# schema_v2_1.net
KiCad netlist of a schematic drawn in EAGLE
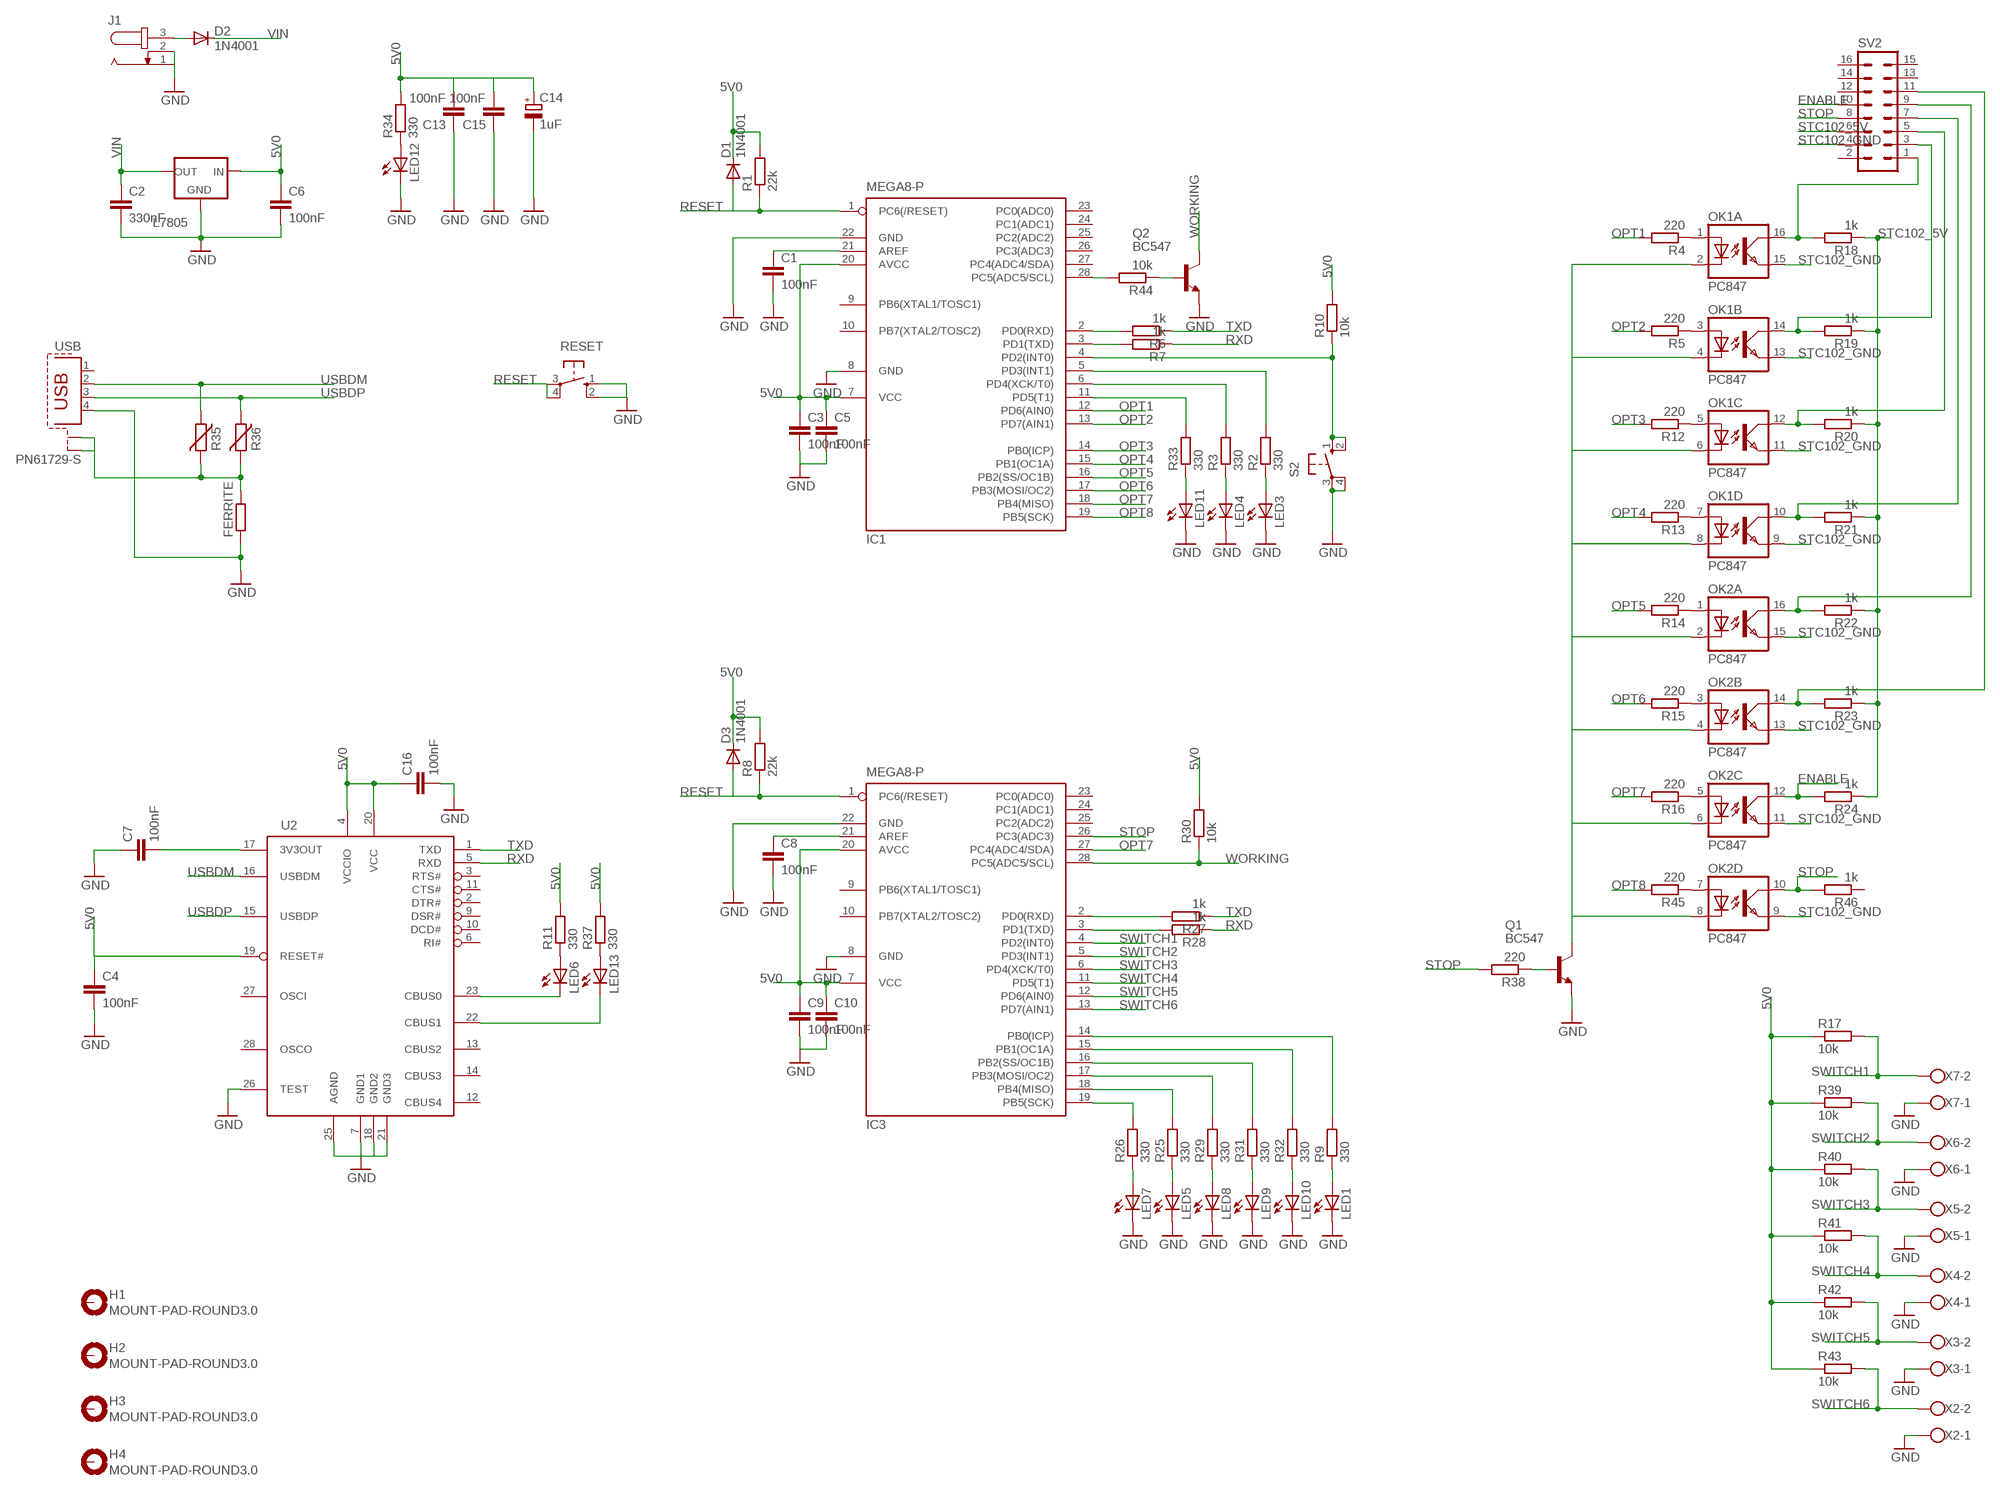
[diagram p0: schematic, sheet 1]

(export (version "E")
  (design (tool "Eeschema 10.0.6"))
  (components
    (comp (ref "C1")
      (value "100nF")
      (footprint "eagle-import:C025-025X050")
      (libsource (lib "eagle-import") (part "C-EU025-025X050"))
    )
    (comp (ref "C2")
      (value "330nF")
      (footprint "eagle-import:C025-025X050")
      (libsource (lib "eagle-import") (part "C-EU025-025X050"))
    )
    (comp (ref "C3")
      (value "100nF")
      (footprint "eagle-import:C025-025X050")
      (libsource (lib "eagle-import") (part "C-EU025-025X050"))
    )
    (comp (ref "C4")
      (value "100nF")
      (footprint "eagle-import:C0603K")
      (libsource (lib "eagle-import") (part "C-EUC0603K"))
    )
    (comp (ref "C5")
      (value "100nF")
      (footprint "eagle-import:C025-025X050")
      (libsource (lib "eagle-import") (part "C-EU025-025X050"))
    )
    (comp (ref "C6")
      (value "100nF")
      (footprint "eagle-import:C025-025X050")
      (libsource (lib "eagle-import") (part "C-EU025-025X050"))
    )
    (comp (ref "C7")
      (value "100nF")
      (footprint "eagle-import:C0603K")
      (libsource (lib "eagle-import") (part "C-EUC0603K"))
    )
    (comp (ref "C8")
      (value "100nF")
      (footprint "eagle-import:C025-025X050")
      (libsource (lib "eagle-import") (part "C-EU025-025X050"))
    )
    (comp (ref "C9")
      (value "100nF")
      (footprint "eagle-import:C025-025X050")
      (libsource (lib "eagle-import") (part "C-EU025-025X050"))
    )
    (comp (ref "C10")
      (value "100nF")
      (footprint "eagle-import:C025-025X050")
      (libsource (lib "eagle-import") (part "C-EU025-025X050"))
    )
    (comp (ref "C13")
      (value "100nF")
      (footprint "eagle-import:C025-025X050")
      (libsource (lib "eagle-import") (part "C-EU025-025X050"))
    )
    (comp (ref "C14")
      (value "1uF")
      (footprint "eagle-import:E2,5-5")
      (libsource (lib "eagle-import") (part "CPOL-EUE2.5-5"))
    )
    (comp (ref "C15")
      (value "100nF")
      (footprint "eagle-import:C025-025X050")
      (libsource (lib "eagle-import") (part "C-EU025-025X050"))
    )
    (comp (ref "C16")
      (value "100nF")
      (footprint "eagle-import:C0603K")
      (libsource (lib "eagle-import") (part "C-EUC0603K"))
    )
    (comp (ref "D1")
      (value "1N4001")
      (footprint "eagle-import:DO41-10")
      (libsource (lib "eagle-import") (part "1N4004"))
    )
    (comp (ref "D2")
      (value "1N4001")
      (footprint "eagle-import:DO41-10")
      (libsource (lib "eagle-import") (part "1N4004"))
    )
    (comp (ref "D3")
      (value "1N4001")
      (footprint "eagle-import:DO41-10")
      (libsource (lib "eagle-import") (part "1N4004"))
    )
    (comp (ref "FERRITE")
      (value "R-EU_M0805")
      (footprint "eagle-import:M0805")
      (libsource (lib "eagle-import") (part "resistor_R-EU_M0805"))
    )
    (comp (ref "H1")
      (value "MOUNT-PAD-ROUND3.0")
      (footprint "eagle-import:3,0-PAD")
      (libsource (lib "eagle-import") (part "MOUNT-PAD-ROUND3.0"))
    )
    (comp (ref "H2")
      (value "MOUNT-PAD-ROUND3.0")
      (footprint "eagle-import:3,0-PAD")
      (libsource (lib "eagle-import") (part "MOUNT-PAD-ROUND3.0"))
    )
    (comp (ref "H3")
      (value "MOUNT-PAD-ROUND3.0")
      (footprint "eagle-import:3,0-PAD")
      (libsource (lib "eagle-import") (part "MOUNT-PAD-ROUND3.0"))
    )
    (comp (ref "H4")
      (value "MOUNT-PAD-ROUND3.0")
      (footprint "eagle-import:3,0-PAD")
      (libsource (lib "eagle-import") (part "MOUNT-PAD-ROUND3.0"))
    )
    (comp (ref "IC1")
      (value "MEGA8-P")
      (footprint "eagle-import:DIL28-3")
      (libsource (lib "eagle-import") (part "MEGA8-P"))
    )
    (comp (ref "IC3")
      (value "MEGA8-P")
      (footprint "eagle-import:DIL28-3")
      (libsource (lib "eagle-import") (part "MEGA8-P"))
    )
    (comp (ref "J1")
      (value "JACK-PLUG0")
      (footprint "eagle-import:SPC4077")
      (libsource (lib "eagle-import") (part "JACK-PLUG0"))
    )
    (comp (ref "L7805")
      (value "79XXS")
      (footprint "eagle-import:79XXS")
      (libsource (lib "eagle-import") (part "79XXS"))
    )
    (comp (ref "LED1")
      (value "LED3MM")
      (footprint "eagle-import:LED3MM")
      (libsource (lib "eagle-import") (part "LED3MM"))
    )
    (comp (ref "LED3")
      (value "LED3MM")
      (footprint "eagle-import:LED3MM")
      (libsource (lib "eagle-import") (part "LED3MM"))
    )
    (comp (ref "LED4")
      (value "LED3MM")
      (footprint "eagle-import:LED3MM")
      (libsource (lib "eagle-import") (part "LED3MM"))
    )
    (comp (ref "LED5")
      (value "LED3MM")
      (footprint "eagle-import:LED3MM")
      (libsource (lib "eagle-import") (part "LED3MM"))
    )
    (comp (ref "LED6")
      (value "LED3MM")
      (footprint "eagle-import:LED3MM")
      (libsource (lib "eagle-import") (part "LED3MM"))
    )
    (comp (ref "LED7")
      (value "LED3MM")
      (footprint "eagle-import:LED3MM")
      (libsource (lib "eagle-import") (part "LED3MM"))
    )
    (comp (ref "LED8")
      (value "LED3MM")
      (footprint "eagle-import:LED3MM")
      (libsource (lib "eagle-import") (part "LED3MM"))
    )
    (comp (ref "LED9")
      (value "LED3MM")
      (footprint "eagle-import:LED3MM")
      (libsource (lib "eagle-import") (part "LED3MM"))
    )
    (comp (ref "LED10")
      (value "LED3MM")
      (footprint "eagle-import:LED3MM")
      (libsource (lib "eagle-import") (part "LED3MM"))
    )
    (comp (ref "LED11")
      (value "LED3MM")
      (footprint "eagle-import:LED3MM")
      (libsource (lib "eagle-import") (part "LED3MM"))
    )
    (comp (ref "LED12")
      (value "LED3MM")
      (footprint "eagle-import:LED3MM")
      (libsource (lib "eagle-import") (part "LED3MM"))
    )
    (comp (ref "LED13")
      (value "LED3MM")
      (footprint "eagle-import:LED3MM")
      (libsource (lib "eagle-import") (part "LED3MM"))
    )
    (comp (ref "OK1")
      (value "PC847")
      (footprint "eagle-import:DIL16")
      (libsource (lib "eagle-import") (part "PC847"))
    )
    (comp (ref "OK2")
      (value "PC847")
      (footprint "eagle-import:DIL16")
      (libsource (lib "eagle-import") (part "PC847"))
    )
    (comp (ref "Q1")
      (value "BC547")
      (footprint "eagle-import:TO92")
      (libsource (lib "eagle-import") (part "BC547"))
    )
    (comp (ref "Q2")
      (value "BC547")
      (footprint "eagle-import:TO92")
      (libsource (lib "eagle-import") (part "BC547"))
    )
    (comp (ref "R1")
      (value "22k")
      (footprint "eagle-import:0207_10")
      (libsource (lib "eagle-import") (part "R-EU_0207/10"))
    )
    (comp (ref "R2")
      (value "330")
      (footprint "eagle-import:0207_10")
      (libsource (lib "eagle-import") (part "R-EU_0207/10"))
    )
    (comp (ref "R3")
      (value "330")
      (footprint "eagle-import:0207_10")
      (libsource (lib "eagle-import") (part "R-EU_0207/10"))
    )
    (comp (ref "R4")
      (value "220")
      (footprint "eagle-import:0207_10")
      (libsource (lib "eagle-import") (part "R-EU_0207/10"))
    )
    (comp (ref "R5")
      (value "220")
      (footprint "eagle-import:0207_10")
      (libsource (lib "eagle-import") (part "R-EU_0207/10"))
    )
    (comp (ref "R6")
      (value "1k")
      (footprint "eagle-import:M1206")
      (libsource (lib "eagle-import") (part "R-EU_M1206"))
    )
    (comp (ref "R7")
      (value "1k")
      (footprint "eagle-import:M1206")
      (libsource (lib "eagle-import") (part "R-EU_M1206"))
    )
    (comp (ref "R8")
      (value "22k")
      (footprint "eagle-import:0207_10")
      (libsource (lib "eagle-import") (part "R-EU_0207/10"))
    )
    (comp (ref "R9")
      (value "330")
      (footprint "eagle-import:0207_10")
      (libsource (lib "eagle-import") (part "R-EU_0207/10"))
    )
    (comp (ref "R10")
      (value "10k")
      (footprint "eagle-import:0207_10")
      (libsource (lib "eagle-import") (part "R-EU_0207/10"))
    )
    (comp (ref "R11")
      (value "330")
      (footprint "eagle-import:0207_10")
      (libsource (lib "eagle-import") (part "R-EU_0207/10"))
    )
    (comp (ref "R12")
      (value "220")
      (footprint "eagle-import:0207_10")
      (libsource (lib "eagle-import") (part "R-EU_0207/10"))
    )
    (comp (ref "R13")
      (value "220")
      (footprint "eagle-import:0207_10")
      (libsource (lib "eagle-import") (part "R-EU_0207/10"))
    )
    (comp (ref "R14")
      (value "220")
      (footprint "eagle-import:0207_10")
      (libsource (lib "eagle-import") (part "R-EU_0207/10"))
    )
    (comp (ref "R15")
      (value "220")
      (footprint "eagle-import:0207_10")
      (libsource (lib "eagle-import") (part "R-EU_0207/10"))
    )
    (comp (ref "R16")
      (value "220")
      (footprint "eagle-import:0207_10")
      (libsource (lib "eagle-import") (part "R-EU_0207/10"))
    )
    (comp (ref "R17")
      (value "10k")
      (footprint "eagle-import:R1206")
      (libsource (lib "eagle-import") (part "R-EU_R1206"))
    )
    (comp (ref "R18")
      (value "1k")
      (footprint "eagle-import:0207_10")
      (libsource (lib "eagle-import") (part "R-EU_0207/10"))
    )
    (comp (ref "R19")
      (value "1k")
      (footprint "eagle-import:0207_10")
      (libsource (lib "eagle-import") (part "R-EU_0207/10"))
    )
    (comp (ref "R20")
      (value "1k")
      (footprint "eagle-import:0207_10")
      (libsource (lib "eagle-import") (part "R-EU_0207/10"))
    )
    (comp (ref "R21")
      (value "1k")
      (footprint "eagle-import:0207_10")
      (libsource (lib "eagle-import") (part "R-EU_0207/10"))
    )
    (comp (ref "R22")
      (value "1k")
      (footprint "eagle-import:0207_10")
      (libsource (lib "eagle-import") (part "R-EU_0207/10"))
    )
    (comp (ref "R23")
      (value "1k")
      (footprint "eagle-import:0207_10")
      (libsource (lib "eagle-import") (part "R-EU_0207/10"))
    )
    (comp (ref "R24")
      (value "1k")
      (footprint "eagle-import:0207_10")
      (libsource (lib "eagle-import") (part "R-EU_0207/10"))
    )
    (comp (ref "R25")
      (value "330")
      (footprint "eagle-import:0207_10")
      (libsource (lib "eagle-import") (part "R-EU_0207/10"))
    )
    (comp (ref "R26")
      (value "330")
      (footprint "eagle-import:0207_10")
      (libsource (lib "eagle-import") (part "R-EU_0207/10"))
    )
    (comp (ref "R27")
      (value "1k")
      (footprint "eagle-import:M1206")
      (libsource (lib "eagle-import") (part "R-EU_M1206"))
    )
    (comp (ref "R28")
      (value "1k")
      (footprint "eagle-import:M1206")
      (libsource (lib "eagle-import") (part "R-EU_M1206"))
    )
    (comp (ref "R29")
      (value "330")
      (footprint "eagle-import:0207_10")
      (libsource (lib "eagle-import") (part "R-EU_0207/10"))
    )
    (comp (ref "R30")
      (value "10k")
      (footprint "eagle-import:0207_10")
      (libsource (lib "eagle-import") (part "R-EU_0207/10"))
    )
    (comp (ref "R31")
      (value "330")
      (footprint "eagle-import:0207_10")
      (libsource (lib "eagle-import") (part "R-EU_0207/10"))
    )
    (comp (ref "R32")
      (value "330")
      (footprint "eagle-import:0207_10")
      (libsource (lib "eagle-import") (part "R-EU_0207/10"))
    )
    (comp (ref "R33")
      (value "330")
      (footprint "eagle-import:0207_10")
      (libsource (lib "eagle-import") (part "R-EU_0207/10"))
    )
    (comp (ref "R34")
      (value "330")
      (footprint "eagle-import:0207_10")
      (libsource (lib "eagle-import") (part "R-EU_0207/10"))
    )
    (comp (ref "R35")
      (value "VARISTORCN0603")
      (footprint "eagle-import:CT_CN0603")
      (libsource (lib "eagle-import") (part "VARISTORCN0603"))
    )
    (comp (ref "R36")
      (value "VARISTORCN0603")
      (footprint "eagle-import:CT_CN0603")
      (libsource (lib "eagle-import") (part "VARISTORCN0603"))
    )
    (comp (ref "R37")
      (value "330")
      (footprint "eagle-import:0207_10")
      (libsource (lib "eagle-import") (part "R-EU_0207/10"))
    )
    (comp (ref "R38")
      (value "220")
      (footprint "eagle-import:0207_10")
      (libsource (lib "eagle-import") (part "R-EU_0207/10"))
    )
    (comp (ref "R39")
      (value "10k")
      (footprint "eagle-import:0207_10")
      (libsource (lib "eagle-import") (part "R-EU_0207/10"))
    )
    (comp (ref "R40")
      (value "10k")
      (footprint "eagle-import:0207_10")
      (libsource (lib "eagle-import") (part "R-EU_0207/10"))
    )
    (comp (ref "R41")
      (value "10k")
      (footprint "eagle-import:0207_10")
      (libsource (lib "eagle-import") (part "R-EU_0207/10"))
    )
    (comp (ref "R42")
      (value "10k")
      (footprint "eagle-import:0207_10")
      (libsource (lib "eagle-import") (part "R-EU_0207/10"))
    )
    (comp (ref "R43")
      (value "10k")
      (footprint "eagle-import:0207_10")
      (libsource (lib "eagle-import") (part "R-EU_0207/10"))
    )
    (comp (ref "R44")
      (value "10k")
      (footprint "eagle-import:0207_10")
      (libsource (lib "eagle-import") (part "R-EU_0207/10"))
    )
    (comp (ref "R45")
      (value "220")
      (footprint "eagle-import:0207_10")
      (libsource (lib "eagle-import") (part "R-EU_0207/10"))
    )
    (comp (ref "R46")
      (value "1k")
      (footprint "eagle-import:0207_10")
      (libsource (lib "eagle-import") (part "R-EU_0207/10"))
    )
    (comp (ref "RESET")
      (value "10-XX")
      (footprint "eagle-import:B3F-10XX")
      (fields (field (name "MPN") "B3F-1000"))
      (libsource (lib "eagle-import") (part "10-XX"))
    )
    (comp (ref "S2")
      (value "10-XX")
      (footprint "eagle-import:B3F-10XX")
      (fields (field (name "MPN") "B3F-1000"))
      (libsource (lib "eagle-import") (part "10-XX"))
    )
    (comp (ref "SV2")
      (value "MA08-2")
      (footprint "eagle-import:MA08-2")
      (libsource (lib "eagle-import") (part "MA08-2"))
    )
    (comp (ref "U2")
      (value "FT232RL")
      (footprint "eagle-import:SSOP28DB")
      (libsource (lib "eagle-import") (part "FT232RL"))
    )
    (comp (ref "USB")
      (value "PN61729-S")
      (footprint "eagle-import:PN61729-S")
      (fields (field (name "OC_FARNELL") "unknown") (field (name "OC_NEWARK") "unknown"))
      (libsource (lib "eagle-import") (part "PN61729-S"))
    )
    (comp (ref "X2")
      (value "W237-102")
      (footprint "eagle-import:W237-102")
      (fields (field (name "MPN") "237-102"))
      (libsource (lib "eagle-import") (part "W237-102"))
    )
    (comp (ref "X3")
      (value "W237-102")
      (footprint "eagle-import:W237-102")
      (fields (field (name "MPN") "237-102"))
      (libsource (lib "eagle-import") (part "W237-102"))
    )
    (comp (ref "X4")
      (value "W237-102")
      (footprint "eagle-import:W237-102")
      (fields (field (name "MPN") "237-102"))
      (libsource (lib "eagle-import") (part "W237-102"))
    )
    (comp (ref "X5")
      (value "W237-102")
      (footprint "eagle-import:W237-102")
      (fields (field (name "MPN") "237-102"))
      (libsource (lib "eagle-import") (part "W237-102"))
    )
    (comp (ref "X6")
      (value "W237-102")
      (footprint "eagle-import:W237-102")
      (fields (field (name "MPN") "237-102"))
      (libsource (lib "eagle-import") (part "W237-102"))
    )
    (comp (ref "X7")
      (value "W237-102")
      (footprint "eagle-import:W237-102")
      (fields (field (name "MPN") "237-102"))
      (libsource (lib "eagle-import") (part "W237-102"))
    )
  )
  (nets
    (net (code "1") (name "/5V0") (class "Default")
      (node (ref "C10") (pin "1") (pinfunction "1_1") (pintype "passive"))
      (node (ref "C13") (pin "2") (pinfunction "2_2") (pintype "passive"))
      (node (ref "C14") (pin "+") (pinfunction "+_+") (pintype "passive"))
      (node (ref "C15") (pin "2") (pinfunction "2_2") (pintype "passive"))
      (node (ref "C16") (pin "1") (pinfunction "1_1") (pintype "passive"))
      (node (ref "C3") (pin "1") (pinfunction "1_1") (pintype "passive"))
      (node (ref "C4") (pin "1") (pinfunction "1_1") (pintype "passive"))
      (node (ref "C5") (pin "1") (pinfunction "1_1") (pintype "passive"))
      (node (ref "C6") (pin "1") (pinfunction "1_1") (pintype "passive"))
      (node (ref "C9") (pin "1") (pinfunction "1_1") (pintype "passive"))
      (node (ref "D1") (pin "C") (pinfunction "C_C") (pintype "passive"))
      (node (ref "D3") (pin "C") (pinfunction "C_C") (pintype "passive"))
      (node (ref "IC1") (pin "20") (pinfunction "AVCC_20") (pintype "power_in"))
      (node (ref "IC1") (pin "7") (pinfunction "VCC_7") (pintype "power_in"))
      (node (ref "IC3") (pin "20") (pinfunction "AVCC_20") (pintype "power_in"))
      (node (ref "IC3") (pin "7") (pinfunction "VCC_7") (pintype "power_in"))
      (node (ref "L7805") (pin "IN") (pinfunction "IN_IN") (pintype "input"))
      (node (ref "R1") (pin "2") (pinfunction "2_2") (pintype "passive"))
      (node (ref "R10") (pin "2") (pinfunction "2_2") (pintype "passive"))
      (node (ref "R11") (pin "2") (pinfunction "2_2") (pintype "passive"))
      (node (ref "R17") (pin "1") (pinfunction "1_1") (pintype "passive"))
      (node (ref "R30") (pin "2") (pinfunction "2_2") (pintype "passive"))
      (node (ref "R34") (pin "2") (pinfunction "2_2") (pintype "passive"))
      (node (ref "R37") (pin "2") (pinfunction "2_2") (pintype "passive"))
      (node (ref "R39") (pin "1") (pinfunction "1_1") (pintype "passive"))
      (node (ref "R40") (pin "1") (pinfunction "1_1") (pintype "passive"))
      (node (ref "R41") (pin "1") (pinfunction "1_1") (pintype "passive"))
      (node (ref "R42") (pin "1") (pinfunction "1_1") (pintype "passive"))
      (node (ref "R43") (pin "1") (pinfunction "1_1") (pintype "passive"))
      (node (ref "R8") (pin "2") (pinfunction "2_2") (pintype "passive"))
      (node (ref "U2") (pin "19") (pinfunction "RESET#_19") (pintype "input"))
      (node (ref "U2") (pin "20") (pinfunction "VCC_20") (pintype "power_in"))
      (node (ref "U2") (pin "4") (pinfunction "VCCIO_4") (pintype "power_in"))
    )
    (net (code "2") (name "/ENABLE") (class "Default")
      (node (ref "OK2") (pin "12") (pinfunction "COL_12") (pintype "passive"))
      (node (ref "R24") (pin "2") (pinfunction "2_2") (pintype "passive"))
      (node (ref "SV2") (pin "10") (pinfunction "10_10") (pintype "passive"))
    )
    (net (code "3") (name "/OPT1") (class "Default")
      (node (ref "IC1") (pin "12") (pinfunction "PD6(AIN0)_12") (pintype "bidirectional"))
      (node (ref "R4") (pin "2") (pinfunction "2_2") (pintype "passive"))
    )
    (net (code "4") (name "/OPT2") (class "Default")
      (node (ref "IC1") (pin "13") (pinfunction "PD7(AIN1)_13") (pintype "bidirectional"))
      (node (ref "R5") (pin "2") (pinfunction "2_2") (pintype "passive"))
    )
    (net (code "5") (name "/OPT3") (class "Default")
      (node (ref "IC1") (pin "14") (pinfunction "PB0(ICP)_14") (pintype "bidirectional"))
      (node (ref "R12") (pin "2") (pinfunction "2_2") (pintype "passive"))
    )
    (net (code "6") (name "/OPT4") (class "Default")
      (node (ref "IC1") (pin "15") (pinfunction "PB1(OC1A)_15") (pintype "bidirectional"))
      (node (ref "R13") (pin "2") (pinfunction "2_2") (pintype "passive"))
    )
    (net (code "7") (name "/OPT5") (class "Default")
      (node (ref "IC1") (pin "16") (pinfunction "PB2(SS/OC1B)_16") (pintype "bidirectional"))
      (node (ref "R14") (pin "2") (pinfunction "2_2") (pintype "passive"))
    )
    (net (code "8") (name "/OPT6") (class "Default")
      (node (ref "IC1") (pin "17") (pinfunction "PB3(MOSI/OC2)_17") (pintype "bidirectional"))
      (node (ref "R15") (pin "2") (pinfunction "2_2") (pintype "passive"))
    )
    (net (code "9") (name "/OPT7") (class "Default")
      (node (ref "IC1") (pin "18") (pinfunction "PB4(MISO)_18") (pintype "bidirectional"))
      (node (ref "IC3") (pin "27") (pinfunction "PC4(ADC4/SDA)_27") (pintype "bidirectional"))
      (node (ref "R16") (pin "2") (pinfunction "2_2") (pintype "passive"))
    )
    (net (code "10") (name "/OPT8") (class "Default")
      (node (ref "IC1") (pin "19") (pinfunction "PB5(SCK)_19") (pintype "bidirectional"))
      (node (ref "R45") (pin "2") (pinfunction "2_2") (pintype "passive"))
    )
    (net (code "11") (name "/RESET") (class "Default")
      (node (ref "D1") (pin "A") (pinfunction "A_A") (pintype "passive"))
      (node (ref "D3") (pin "A") (pinfunction "A_A") (pintype "passive"))
      (node (ref "IC1") (pin "1") (pinfunction "PC6(/RESET)_1") (pintype "bidirectional"))
      (node (ref "IC3") (pin "1") (pinfunction "PC6(/RESET)_1") (pintype "bidirectional"))
      (node (ref "R1") (pin "1") (pinfunction "1_1") (pintype "passive"))
      (node (ref "R8") (pin "1") (pinfunction "1_1") (pintype "passive"))
      (node (ref "RESET") (pin "3") (pinfunction "P_3") (pintype "passive"))
      (node (ref "RESET") (pin "4") (pinfunction "P1_4") (pintype "passive"))
    )
    (net (code "12") (name "/RXD") (class "Default")
      (node (ref "R28") (pin "1") (pinfunction "1_1") (pintype "passive"))
      (node (ref "R7") (pin "1") (pinfunction "1_1") (pintype "passive"))
      (node (ref "U2") (pin "5") (pinfunction "RXD_5") (pintype "input"))
    )
    (net (code "13") (name "/STC102_5V") (class "Default")
      (node (ref "R18") (pin "1") (pinfunction "1_1") (pintype "passive"))
      (node (ref "R19") (pin "1") (pinfunction "1_1") (pintype "passive"))
      (node (ref "R20") (pin "1") (pinfunction "1_1") (pintype "passive"))
      (node (ref "R21") (pin "1") (pinfunction "1_1") (pintype "passive"))
      (node (ref "R22") (pin "1") (pinfunction "1_1") (pintype "passive"))
      (node (ref "R23") (pin "1") (pinfunction "1_1") (pintype "passive"))
      (node (ref "R24") (pin "1") (pinfunction "1_1") (pintype "passive"))
      (node (ref "SV2") (pin "6") (pinfunction "6_6") (pintype "passive"))
    )
    (net (code "14") (name "/STC102_GND") (class "Default")
      (node (ref "OK1") (pin "11") (pinfunction "EMIT_11") (pintype "passive"))
      (node (ref "OK1") (pin "13") (pinfunction "EMIT_13") (pintype "passive"))
      (node (ref "OK1") (pin "15") (pinfunction "EMIT_15") (pintype "passive"))
      (node (ref "OK1") (pin "9") (pinfunction "EMIT_9") (pintype "passive"))
      (node (ref "OK2") (pin "11") (pinfunction "EMIT_11") (pintype "passive"))
      (node (ref "OK2") (pin "13") (pinfunction "EMIT_13") (pintype "passive"))
      (node (ref "OK2") (pin "15") (pinfunction "EMIT_15") (pintype "passive"))
      (node (ref "OK2") (pin "9") (pinfunction "EMIT_9") (pintype "passive"))
      (node (ref "SV2") (pin "4") (pinfunction "4_4") (pintype "passive"))
    )
    (net (code "15") (name "/STOP") (class "Default")
      (node (ref "IC3") (pin "26") (pinfunction "PC3(ADC3)_26") (pintype "bidirectional"))
      (node (ref "OK2") (pin "10") (pinfunction "COL_10") (pintype "passive"))
      (node (ref "R38") (pin "2") (pinfunction "2_2") (pintype "passive"))
      (node (ref "R46") (pin "2") (pinfunction "2_2") (pintype "passive"))
      (node (ref "SV2") (pin "8") (pinfunction "8_8") (pintype "passive"))
    )
    (net (code "16") (name "/SWITCH1") (class "Default")
      (node (ref "IC3") (pin "4") (pinfunction "PD2(INT0)_4") (pintype "bidirectional"))
      (node (ref "R17") (pin "2") (pinfunction "2_2") (pintype "passive"))
      (node (ref "X7") (pin "2") (pinfunction "KL_2") (pintype "passive"))
    )
    (net (code "17") (name "/SWITCH2") (class "Default")
      (node (ref "IC3") (pin "5") (pinfunction "PD3(INT1)_5") (pintype "bidirectional"))
      (node (ref "R39") (pin "2") (pinfunction "2_2") (pintype "passive"))
      (node (ref "X6") (pin "2") (pinfunction "KL_2") (pintype "passive"))
    )
    (net (code "18") (name "/SWITCH3") (class "Default")
      (node (ref "IC3") (pin "6") (pinfunction "PD4(XCK/T0)_6") (pintype "bidirectional"))
      (node (ref "R40") (pin "2") (pinfunction "2_2") (pintype "passive"))
      (node (ref "X5") (pin "2") (pinfunction "KL_2") (pintype "passive"))
    )
    (net (code "19") (name "/SWITCH4") (class "Default")
      (node (ref "IC3") (pin "11") (pinfunction "PD5(T1)_11") (pintype "bidirectional"))
      (node (ref "R41") (pin "2") (pinfunction "2_2") (pintype "passive"))
      (node (ref "X4") (pin "2") (pinfunction "KL_2") (pintype "passive"))
    )
    (net (code "20") (name "/SWITCH5") (class "Default")
      (node (ref "IC3") (pin "12") (pinfunction "PD6(AIN0)_12") (pintype "bidirectional"))
      (node (ref "R42") (pin "2") (pinfunction "2_2") (pintype "passive"))
      (node (ref "X3") (pin "2") (pinfunction "KL_2") (pintype "passive"))
    )
    (net (code "21") (name "/SWITCH6") (class "Default")
      (node (ref "IC3") (pin "13") (pinfunction "PD7(AIN1)_13") (pintype "bidirectional"))
      (node (ref "R43") (pin "2") (pinfunction "2_2") (pintype "passive"))
      (node (ref "X2") (pin "2") (pinfunction "KL_2") (pintype "passive"))
    )
    (net (code "22") (name "/TXD") (class "Default")
      (node (ref "R27") (pin "1") (pinfunction "1_1") (pintype "passive"))
      (node (ref "R6") (pin "1") (pinfunction "1_1") (pintype "passive"))
      (node (ref "U2") (pin "1") (pinfunction "TXD_1") (pintype "output"))
    )
    (net (code "23") (name "/USBDM") (class "Default")
      (node (ref "R35") (pin "1") (pinfunction "1_1") (pintype "passive"))
      (node (ref "U2") (pin "16") (pinfunction "USBDM_16") (pintype "bidirectional"))
      (node (ref "USB") (pin "2") (pinfunction "2_2") (pintype "passive"))
    )
    (net (code "24") (name "/USBDP") (class "Default")
      (node (ref "R36") (pin "1") (pinfunction "1_1") (pintype "passive"))
      (node (ref "U2") (pin "15") (pinfunction "USBDP_15") (pintype "bidirectional"))
      (node (ref "USB") (pin "3") (pinfunction "3_3") (pintype "passive"))
    )
    (net (code "25") (name "/VIN") (class "Default")
      (node (ref "C2") (pin "1") (pinfunction "1_1") (pintype "passive"))
      (node (ref "D2") (pin "C") (pinfunction "C_C") (pintype "passive"))
      (node (ref "L7805") (pin "OUT") (pinfunction "OUT_OUT") (pintype "passive"))
    )
    (net (code "26") (name "/WORKING") (class "Default")
      (node (ref "IC3") (pin "28") (pinfunction "PC5(ADC5/SCL)_28") (pintype "bidirectional"))
      (node (ref "Q2") (pin "3") (pinfunction "C_3") (pintype "passive"))
      (node (ref "R30") (pin "1") (pinfunction "1_1") (pintype "passive"))
    )
    (net (code "27") (name "GND") (class "Default")
      (node (ref "C1") (pin "2") (pinfunction "2_2") (pintype "passive"))
      (node (ref "C10") (pin "2") (pinfunction "2_2") (pintype "passive"))
      (node (ref "C13") (pin "1") (pinfunction "1_1") (pintype "passive"))
      (node (ref "C14") (pin "-") (pinfunction "-_-") (pintype "passive"))
      (node (ref "C15") (pin "1") (pinfunction "1_1") (pintype "passive"))
      (node (ref "C16") (pin "2") (pinfunction "2_2") (pintype "passive"))
      (node (ref "C2") (pin "2") (pinfunction "2_2") (pintype "passive"))
      (node (ref "C3") (pin "2") (pinfunction "2_2") (pintype "passive"))
      (node (ref "C4") (pin "2") (pinfunction "2_2") (pintype "passive"))
      (node (ref "C5") (pin "2") (pinfunction "2_2") (pintype "passive"))
      (node (ref "C6") (pin "2") (pinfunction "2_2") (pintype "passive"))
      (node (ref "C7") (pin "1") (pinfunction "1_1") (pintype "passive"))
      (node (ref "C8") (pin "2") (pinfunction "2_2") (pintype "passive"))
      (node (ref "C9") (pin "2") (pinfunction "2_2") (pintype "passive"))
      (node (ref "FERRITE") (pin "1") (pinfunction "1_1") (pintype "passive"))
      (node (ref "IC1") (pin "22") (pinfunction "GND_22") (pintype "power_in"))
      (node (ref "IC1") (pin "8") (pinfunction "GND_8") (pintype "power_in"))
      (node (ref "IC3") (pin "22") (pinfunction "GND_22") (pintype "power_in"))
      (node (ref "IC3") (pin "8") (pinfunction "GND_8") (pintype "power_in"))
      (node (ref "J1") (pin "1") (pinfunction "1_1") (pintype "passive"))
      (node (ref "J1") (pin "2") (pinfunction "2_2") (pintype "passive"))
      (node (ref "L7805") (pin "GND") (pinfunction "GND_GND") (pintype "input"))
      (node (ref "LED1") (pin "K") (pinfunction "C_K") (pintype "passive"))
      (node (ref "LED10") (pin "K") (pinfunction "C_K") (pintype "passive"))
      (node (ref "LED11") (pin "K") (pinfunction "C_K") (pintype "passive"))
      (node (ref "LED12") (pin "K") (pinfunction "C_K") (pintype "passive"))
      (node (ref "LED3") (pin "K") (pinfunction "C_K") (pintype "passive"))
      (node (ref "LED4") (pin "K") (pinfunction "C_K") (pintype "passive"))
      (node (ref "LED5") (pin "K") (pinfunction "C_K") (pintype "passive"))
      (node (ref "LED7") (pin "K") (pinfunction "C_K") (pintype "passive"))
      (node (ref "LED8") (pin "K") (pinfunction "C_K") (pintype "passive"))
      (node (ref "LED9") (pin "K") (pinfunction "C_K") (pintype "passive"))
      (node (ref "Q1") (pin "1") (pinfunction "E_1") (pintype "passive"))
      (node (ref "Q2") (pin "1") (pinfunction "E_1") (pintype "passive"))
      (node (ref "RESET") (pin "1") (pinfunction "S_1") (pintype "passive"))
      (node (ref "RESET") (pin "2") (pinfunction "S1_2") (pintype "passive"))
      (node (ref "S2") (pin "3") (pinfunction "P_3") (pintype "passive"))
      (node (ref "S2") (pin "4") (pinfunction "P1_4") (pintype "passive"))
      (node (ref "U2") (pin "18") (pinfunction "GND2_18") (pintype "power_in"))
      (node (ref "U2") (pin "21") (pinfunction "GND3_21") (pintype "power_in"))
      (node (ref "U2") (pin "25") (pinfunction "AGND_25") (pintype "power_in"))
      (node (ref "U2") (pin "26") (pinfunction "TEST_26") (pintype "input"))
      (node (ref "U2") (pin "7") (pinfunction "GND1_7") (pintype "power_in"))
      (node (ref "USB") (pin "4") (pinfunction "4_4") (pintype "passive"))
      (node (ref "X2") (pin "1") (pinfunction "KL_1") (pintype "passive"))
      (node (ref "X3") (pin "1") (pinfunction "KL_1") (pintype "passive"))
      (node (ref "X4") (pin "1") (pinfunction "KL_1") (pintype "passive"))
      (node (ref "X5") (pin "1") (pinfunction "KL_1") (pintype "passive"))
      (node (ref "X6") (pin "1") (pinfunction "KL_1") (pintype "passive"))
      (node (ref "X7") (pin "1") (pinfunction "KL_1") (pintype "passive"))
    )
    (net (code "28") (name "Net-(D2-PadA)") (class "Default")
      (node (ref "D2") (pin "A") (pinfunction "A_A") (pintype "passive"))
      (node (ref "J1") (pin "3") (pinfunction "3_3") (pintype "passive"))
    )
    (net (code "29") (name "Net-(FERRITE-Pad2)") (class "Default")
      (node (ref "FERRITE") (pin "2") (pinfunction "2_2") (pintype "passive"))
      (node (ref "R35") (pin "2") (pinfunction "2_2") (pintype "passive"))
      (node (ref "R36") (pin "2") (pinfunction "2_2") (pintype "passive"))
      (node (ref "USB") (pin "S1") (pinfunction "S1_S1") (pintype "passive"))
      (node (ref "USB") (pin "S2") (pinfunction "S2_S2") (pintype "passive"))
    )
    (net (code "30") (name "Net-(IC1-AREF)") (class "Default")
      (node (ref "C1") (pin "1") (pinfunction "1_1") (pintype "passive"))
      (node (ref "IC1") (pin "21") (pinfunction "AREF_21") (pintype "passive"))
    )
    (net (code "31") (name "Net-(IC1-PC5(ADC5{slash}SCL))") (class "Default")
      (node (ref "IC1") (pin "28") (pinfunction "PC5(ADC5/SCL)_28") (pintype "bidirectional"))
      (node (ref "R44") (pin "2") (pinfunction "2_2") (pintype "passive"))
    )
    (net (code "32") (name "Net-(IC1-PD0(RXD))") (class "Default")
      (node (ref "IC1") (pin "2") (pinfunction "PD0(RXD)_2") (pintype "bidirectional"))
      (node (ref "R6") (pin "2") (pinfunction "2_2") (pintype "passive"))
    )
    (net (code "33") (name "Net-(IC1-PD1(TXD))") (class "Default")
      (node (ref "IC1") (pin "3") (pinfunction "PD1(TXD)_3") (pintype "bidirectional"))
      (node (ref "R7") (pin "2") (pinfunction "2_2") (pintype "passive"))
    )
    (net (code "34") (name "Net-(IC1-PD2(INT0))") (class "Default")
      (node (ref "IC1") (pin "4") (pinfunction "PD2(INT0)_4") (pintype "bidirectional"))
      (node (ref "R10") (pin "1") (pinfunction "1_1") (pintype "passive"))
      (node (ref "S2") (pin "1") (pinfunction "S_1") (pintype "passive"))
      (node (ref "S2") (pin "2") (pinfunction "S1_2") (pintype "passive"))
    )
    (net (code "35") (name "Net-(IC1-PD3(INT1))") (class "Default")
      (node (ref "IC1") (pin "5") (pinfunction "PD3(INT1)_5") (pintype "bidirectional"))
      (node (ref "R2") (pin "2") (pinfunction "2_2") (pintype "passive"))
    )
    (net (code "36") (name "Net-(IC1-PD4(XCK{slash}T0))") (class "Default")
      (node (ref "IC1") (pin "6") (pinfunction "PD4(XCK/T0)_6") (pintype "bidirectional"))
      (node (ref "R3") (pin "2") (pinfunction "2_2") (pintype "passive"))
    )
    (net (code "37") (name "Net-(IC1-PD5(T1))") (class "Default")
      (node (ref "IC1") (pin "11") (pinfunction "PD5(T1)_11") (pintype "bidirectional"))
      (node (ref "R33") (pin "2") (pinfunction "2_2") (pintype "passive"))
    )
    (net (code "38") (name "Net-(IC3-AREF)") (class "Default")
      (node (ref "C8") (pin "1") (pinfunction "1_1") (pintype "passive"))
      (node (ref "IC3") (pin "21") (pinfunction "AREF_21") (pintype "passive"))
    )
    (net (code "39") (name "Net-(IC3-PB0(ICP))") (class "Default")
      (node (ref "IC3") (pin "14") (pinfunction "PB0(ICP)_14") (pintype "bidirectional"))
      (node (ref "R9") (pin "2") (pinfunction "2_2") (pintype "passive"))
    )
    (net (code "40") (name "Net-(IC3-PB1(OC1A))") (class "Default")
      (node (ref "IC3") (pin "15") (pinfunction "PB1(OC1A)_15") (pintype "bidirectional"))
      (node (ref "R32") (pin "2") (pinfunction "2_2") (pintype "passive"))
    )
    (net (code "41") (name "Net-(IC3-PB2(SS{slash}OC1B))") (class "Default")
      (node (ref "IC3") (pin "16") (pinfunction "PB2(SS/OC1B)_16") (pintype "bidirectional"))
      (node (ref "R31") (pin "2") (pinfunction "2_2") (pintype "passive"))
    )
    (net (code "42") (name "Net-(IC3-PB3(MOSI{slash}OC2))") (class "Default")
      (node (ref "IC3") (pin "17") (pinfunction "PB3(MOSI/OC2)_17") (pintype "bidirectional"))
      (node (ref "R29") (pin "2") (pinfunction "2_2") (pintype "passive"))
    )
    (net (code "43") (name "Net-(IC3-PB4(MISO))") (class "Default")
      (node (ref "IC3") (pin "18") (pinfunction "PB4(MISO)_18") (pintype "bidirectional"))
      (node (ref "R25") (pin "2") (pinfunction "2_2") (pintype "passive"))
    )
    (net (code "44") (name "Net-(IC3-PB5(SCK))") (class "Default")
      (node (ref "IC3") (pin "19") (pinfunction "PB5(SCK)_19") (pintype "bidirectional"))
      (node (ref "R26") (pin "2") (pinfunction "2_2") (pintype "passive"))
    )
    (net (code "45") (name "Net-(IC3-PD0(RXD))") (class "Default")
      (node (ref "IC3") (pin "2") (pinfunction "PD0(RXD)_2") (pintype "bidirectional"))
      (node (ref "R27") (pin "2") (pinfunction "2_2") (pintype "passive"))
    )
    (net (code "46") (name "Net-(IC3-PD1(TXD))") (class "Default")
      (node (ref "IC3") (pin "3") (pinfunction "PD1(TXD)_3") (pintype "bidirectional"))
      (node (ref "R28") (pin "2") (pinfunction "2_2") (pintype "passive"))
    )
    (net (code "47") (name "Net-(LED1-PadA)") (class "Default")
      (node (ref "LED1") (pin "A") (pinfunction "A_A") (pintype "passive"))
      (node (ref "R9") (pin "1") (pinfunction "1_1") (pintype "passive"))
    )
    (net (code "48") (name "Net-(LED3-PadA)") (class "Default")
      (node (ref "LED3") (pin "A") (pinfunction "A_A") (pintype "passive"))
      (node (ref "R2") (pin "1") (pinfunction "1_1") (pintype "passive"))
    )
    (net (code "49") (name "Net-(LED4-PadA)") (class "Default")
      (node (ref "LED4") (pin "A") (pinfunction "A_A") (pintype "passive"))
      (node (ref "R3") (pin "1") (pinfunction "1_1") (pintype "passive"))
    )
    (net (code "50") (name "Net-(LED5-PadA)") (class "Default")
      (node (ref "LED5") (pin "A") (pinfunction "A_A") (pintype "passive"))
      (node (ref "R25") (pin "1") (pinfunction "1_1") (pintype "passive"))
    )
    (net (code "51") (name "Net-(LED6-C)") (class "Default")
      (node (ref "LED6") (pin "K") (pinfunction "C_K") (pintype "passive"))
      (node (ref "U2") (pin "23") (pinfunction "CBUS0_23") (pintype "bidirectional"))
    )
    (net (code "52") (name "Net-(LED6-PadA)") (class "Default")
      (node (ref "LED6") (pin "A") (pinfunction "A_A") (pintype "passive"))
      (node (ref "R11") (pin "1") (pinfunction "1_1") (pintype "passive"))
    )
    (net (code "53") (name "Net-(LED7-PadA)") (class "Default")
      (node (ref "LED7") (pin "A") (pinfunction "A_A") (pintype "passive"))
      (node (ref "R26") (pin "1") (pinfunction "1_1") (pintype "passive"))
    )
    (net (code "54") (name "Net-(LED8-PadA)") (class "Default")
      (node (ref "LED8") (pin "A") (pinfunction "A_A") (pintype "passive"))
      (node (ref "R29") (pin "1") (pinfunction "1_1") (pintype "passive"))
    )
    (net (code "55") (name "Net-(LED9-PadA)") (class "Default")
      (node (ref "LED9") (pin "A") (pinfunction "A_A") (pintype "passive"))
      (node (ref "R31") (pin "1") (pinfunction "1_1") (pintype "passive"))
    )
    (net (code "56") (name "Net-(LED10-PadA)") (class "Default")
      (node (ref "LED10") (pin "A") (pinfunction "A_A") (pintype "passive"))
      (node (ref "R32") (pin "1") (pinfunction "1_1") (pintype "passive"))
    )
    (net (code "57") (name "Net-(LED11-PadA)") (class "Default")
      (node (ref "LED11") (pin "A") (pinfunction "A_A") (pintype "passive"))
      (node (ref "R33") (pin "1") (pinfunction "1_1") (pintype "passive"))
    )
    (net (code "58") (name "Net-(LED12-PadA)") (class "Default")
      (node (ref "LED12") (pin "A") (pinfunction "A_A") (pintype "passive"))
      (node (ref "R34") (pin "1") (pinfunction "1_1") (pintype "passive"))
    )
    (net (code "59") (name "Net-(LED13-C)") (class "Default")
      (node (ref "LED13") (pin "K") (pinfunction "C_K") (pintype "passive"))
      (node (ref "U2") (pin "22") (pinfunction "CBUS1_22") (pintype "bidirectional"))
    )
    (net (code "60") (name "Net-(LED13-PadA)") (class "Default")
      (node (ref "LED13") (pin "A") (pinfunction "A_A") (pintype "passive"))
      (node (ref "R37") (pin "1") (pinfunction "1_1") (pintype "passive"))
    )
    (net (code "61") (name "Net-(OK1A-A)") (class "Default")
      (node (ref "OK1") (pin "1") (pinfunction "A_1") (pintype "passive"))
      (node (ref "R4") (pin "1") (pinfunction "1_1") (pintype "passive"))
    )
    (net (code "62") (name "Net-(OK1A-C)") (class "Default")
      (node (ref "OK1") (pin "2") (pinfunction "C_2") (pintype "passive"))
      (node (ref "OK1") (pin "4") (pinfunction "C_4") (pintype "passive"))
      (node (ref "OK1") (pin "6") (pinfunction "C_6") (pintype "passive"))
      (node (ref "OK1") (pin "8") (pinfunction "C_8") (pintype "passive"))
      (node (ref "OK2") (pin "2") (pinfunction "C_2") (pintype "passive"))
      (node (ref "OK2") (pin "4") (pinfunction "C_4") (pintype "passive"))
      (node (ref "OK2") (pin "6") (pinfunction "C_6") (pintype "passive"))
      (node (ref "OK2") (pin "8") (pinfunction "C_8") (pintype "passive"))
      (node (ref "Q1") (pin "3") (pinfunction "C_3") (pintype "passive"))
    )
    (net (code "63") (name "Net-(OK1A-COL)") (class "Default")
      (node (ref "OK1") (pin "16") (pinfunction "COL_16") (pintype "passive"))
      (node (ref "R18") (pin "2") (pinfunction "2_2") (pintype "passive"))
      (node (ref "SV2") (pin "1") (pinfunction "1_1") (pintype "passive"))
    )
    (net (code "64") (name "Net-(OK1B-A)") (class "Default")
      (node (ref "OK1") (pin "3") (pinfunction "A_3") (pintype "passive"))
      (node (ref "R5") (pin "1") (pinfunction "1_1") (pintype "passive"))
    )
    (net (code "65") (name "Net-(OK1B-COL)") (class "Default")
      (node (ref "OK1") (pin "14") (pinfunction "COL_14") (pintype "passive"))
      (node (ref "R19") (pin "2") (pinfunction "2_2") (pintype "passive"))
      (node (ref "SV2") (pin "3") (pinfunction "3_3") (pintype "passive"))
    )
    (net (code "66") (name "Net-(OK1C-A)") (class "Default")
      (node (ref "OK1") (pin "5") (pinfunction "A_5") (pintype "passive"))
      (node (ref "R12") (pin "1") (pinfunction "1_1") (pintype "passive"))
    )
    (net (code "67") (name "Net-(OK1C-COL)") (class "Default")
      (node (ref "OK1") (pin "12") (pinfunction "COL_12") (pintype "passive"))
      (node (ref "R20") (pin "2") (pinfunction "2_2") (pintype "passive"))
      (node (ref "SV2") (pin "5") (pinfunction "5_5") (pintype "passive"))
    )
    (net (code "68") (name "Net-(OK1D-A)") (class "Default")
      (node (ref "OK1") (pin "7") (pinfunction "A_7") (pintype "passive"))
      (node (ref "R13") (pin "1") (pinfunction "1_1") (pintype "passive"))
    )
    (net (code "69") (name "Net-(OK1D-COL)") (class "Default")
      (node (ref "OK1") (pin "10") (pinfunction "COL_10") (pintype "passive"))
      (node (ref "R21") (pin "2") (pinfunction "2_2") (pintype "passive"))
      (node (ref "SV2") (pin "7") (pinfunction "7_7") (pintype "passive"))
    )
    (net (code "70") (name "Net-(OK2A-A)") (class "Default")
      (node (ref "OK2") (pin "1") (pinfunction "A_1") (pintype "passive"))
      (node (ref "R14") (pin "1") (pinfunction "1_1") (pintype "passive"))
    )
    (net (code "71") (name "Net-(OK2A-COL)") (class "Default")
      (node (ref "OK2") (pin "16") (pinfunction "COL_16") (pintype "passive"))
      (node (ref "R22") (pin "2") (pinfunction "2_2") (pintype "passive"))
      (node (ref "SV2") (pin "9") (pinfunction "9_9") (pintype "passive"))
    )
    (net (code "72") (name "Net-(OK2B-A)") (class "Default")
      (node (ref "OK2") (pin "3") (pinfunction "A_3") (pintype "passive"))
      (node (ref "R15") (pin "1") (pinfunction "1_1") (pintype "passive"))
    )
    (net (code "73") (name "Net-(OK2B-COL)") (class "Default")
      (node (ref "OK2") (pin "14") (pinfunction "COL_14") (pintype "passive"))
      (node (ref "R23") (pin "2") (pinfunction "2_2") (pintype "passive"))
      (node (ref "SV2") (pin "11") (pinfunction "11_11") (pintype "passive"))
    )
    (net (code "74") (name "Net-(OK2C-A)") (class "Default")
      (node (ref "OK2") (pin "5") (pinfunction "A_5") (pintype "passive"))
      (node (ref "R16") (pin "1") (pinfunction "1_1") (pintype "passive"))
    )
    (net (code "75") (name "Net-(OK2D-A)") (class "Default")
      (node (ref "OK2") (pin "7") (pinfunction "A_7") (pintype "passive"))
      (node (ref "R45") (pin "1") (pinfunction "1_1") (pintype "passive"))
    )
    (net (code "76") (name "Net-(Q1-B)") (class "Default")
      (node (ref "Q1") (pin "2") (pinfunction "B_2") (pintype "passive"))
      (node (ref "R38") (pin "1") (pinfunction "1_1") (pintype "passive"))
    )
    (net (code "77") (name "Net-(Q2-B)") (class "Default")
      (node (ref "Q2") (pin "2") (pinfunction "B_2") (pintype "passive"))
      (node (ref "R44") (pin "1") (pinfunction "1_1") (pintype "passive"))
    )
    (net (code "78") (name "Net-(U2-3V3OUT)") (class "Default")
      (node (ref "C7") (pin "2") (pinfunction "2_2") (pintype "passive"))
      (node (ref "U2") (pin "17") (pinfunction "3V3OUT_17") (pintype "output"))
    )
    (net (code "79") (name "unconnected-(H1-MOUNT-PadB3,0)") (class "Default")
      (node (ref "H1") (pin "B3,0") (pinfunction "MOUNT_B3,0") (pintype "passive"))
    )
    (net (code "80") (name "unconnected-(H2-MOUNT-PadB3,0)") (class "Default")
      (node (ref "H2") (pin "B3,0") (pinfunction "MOUNT_B3,0") (pintype "passive"))
    )
    (net (code "81") (name "unconnected-(H3-MOUNT-PadB3,0)") (class "Default")
      (node (ref "H3") (pin "B3,0") (pinfunction "MOUNT_B3,0") (pintype "passive"))
    )
    (net (code "82") (name "unconnected-(H4-MOUNT-PadB3,0)") (class "Default")
      (node (ref "H4") (pin "B3,0") (pinfunction "MOUNT_B3,0") (pintype "passive"))
    )
    (net (code "83") (name "unconnected-(IC1-PB6(XTAL1{slash}TOSC1)-Pad9)") (class "Default")
      (node (ref "IC1") (pin "9") (pinfunction "PB6(XTAL1/TOSC1)_9") (pintype "bidirectional"))
    )
    (net (code "84") (name "unconnected-(IC1-PB7(XTAL2{slash}TOSC2)-Pad10)") (class "Default")
      (node (ref "IC1") (pin "10") (pinfunction "PB7(XTAL2/TOSC2)_10") (pintype "bidirectional"))
    )
    (net (code "85") (name "unconnected-(IC1-PC0(ADC0)-Pad23)") (class "Default")
      (node (ref "IC1") (pin "23") (pinfunction "PC0(ADC0)_23") (pintype "bidirectional"))
    )
    (net (code "86") (name "unconnected-(IC1-PC1(ADC1)-Pad24)") (class "Default")
      (node (ref "IC1") (pin "24") (pinfunction "PC1(ADC1)_24") (pintype "bidirectional"))
    )
    (net (code "87") (name "unconnected-(IC1-PC2(ADC2)-Pad25)") (class "Default")
      (node (ref "IC1") (pin "25") (pinfunction "PC2(ADC2)_25") (pintype "bidirectional"))
    )
    (net (code "88") (name "unconnected-(IC1-PC3(ADC3)-Pad26)") (class "Default")
      (node (ref "IC1") (pin "26") (pinfunction "PC3(ADC3)_26") (pintype "bidirectional"))
    )
    (net (code "89") (name "unconnected-(IC1-PC4(ADC4{slash}SDA)-Pad27)") (class "Default")
      (node (ref "IC1") (pin "27") (pinfunction "PC4(ADC4/SDA)_27") (pintype "bidirectional"))
    )
    (net (code "90") (name "unconnected-(IC3-PB6(XTAL1{slash}TOSC1)-Pad9)") (class "Default")
      (node (ref "IC3") (pin "9") (pinfunction "PB6(XTAL1/TOSC1)_9") (pintype "bidirectional"))
    )
    (net (code "91") (name "unconnected-(IC3-PB7(XTAL2{slash}TOSC2)-Pad10)") (class "Default")
      (node (ref "IC3") (pin "10") (pinfunction "PB7(XTAL2/TOSC2)_10") (pintype "bidirectional"))
    )
    (net (code "92") (name "unconnected-(IC3-PC0(ADC0)-Pad23)") (class "Default")
      (node (ref "IC3") (pin "23") (pinfunction "PC0(ADC0)_23") (pintype "bidirectional"))
    )
    (net (code "93") (name "unconnected-(IC3-PC1(ADC1)-Pad24)") (class "Default")
      (node (ref "IC3") (pin "24") (pinfunction "PC1(ADC1)_24") (pintype "bidirectional"))
    )
    (net (code "94") (name "unconnected-(IC3-PC2(ADC2)-Pad25)") (class "Default")
      (node (ref "IC3") (pin "25") (pinfunction "PC2(ADC2)_25") (pintype "bidirectional"))
    )
    (net (code "95") (name "unconnected-(R46-Pad1)") (class "Default")
      (node (ref "R46") (pin "1") (pinfunction "1_1") (pintype "passive"))
    )
    (net (code "96") (name "unconnected-(SV2-Pad2)") (class "Default")
      (node (ref "SV2") (pin "2") (pinfunction "2_2") (pintype "passive"))
    )
    (net (code "97") (name "unconnected-(SV2-Pad12)") (class "Default")
      (node (ref "SV2") (pin "12") (pinfunction "12_12") (pintype "passive"))
    )
    (net (code "98") (name "unconnected-(SV2-Pad13)") (class "Default")
      (node (ref "SV2") (pin "13") (pinfunction "13_13") (pintype "passive"))
    )
    (net (code "99") (name "unconnected-(SV2-Pad14)") (class "Default")
      (node (ref "SV2") (pin "14") (pinfunction "14_14") (pintype "passive"))
    )
    (net (code "100") (name "unconnected-(SV2-Pad15)") (class "Default")
      (node (ref "SV2") (pin "15") (pinfunction "15_15") (pintype "passive"))
    )
    (net (code "101") (name "unconnected-(SV2-Pad16)") (class "Default")
      (node (ref "SV2") (pin "16") (pinfunction "16_16") (pintype "passive"))
    )
    (net (code "102") (name "unconnected-(U2-CBUS2-Pad13)") (class "Default")
      (node (ref "U2") (pin "13") (pinfunction "CBUS2_13") (pintype "bidirectional"))
    )
    (net (code "103") (name "unconnected-(U2-CBUS3-Pad14)") (class "Default")
      (node (ref "U2") (pin "14") (pinfunction "CBUS3_14") (pintype "bidirectional"))
    )
    (net (code "104") (name "unconnected-(U2-CBUS4-Pad12)") (class "Default")
      (node (ref "U2") (pin "12") (pinfunction "CBUS4_12") (pintype "bidirectional"))
    )
    (net (code "105") (name "unconnected-(U2-CTS#-Pad11)") (class "Default")
      (node (ref "U2") (pin "11") (pinfunction "CTS#_11") (pintype "input"))
    )
    (net (code "106") (name "unconnected-(U2-DCD#-Pad10)") (class "Default")
      (node (ref "U2") (pin "10") (pinfunction "DCD#_10") (pintype "input"))
    )
    (net (code "107") (name "unconnected-(U2-DSR#-Pad9)") (class "Default")
      (node (ref "U2") (pin "9") (pinfunction "DSR#_9") (pintype "input"))
    )
    (net (code "108") (name "unconnected-(U2-DTR#-Pad2)") (class "Default")
      (node (ref "U2") (pin "2") (pinfunction "DTR#_2") (pintype "output"))
    )
    (net (code "109") (name "unconnected-(U2-OSCI-Pad27)") (class "Default")
      (node (ref "U2") (pin "27") (pinfunction "OSCI_27") (pintype "input"))
    )
    (net (code "110") (name "unconnected-(U2-OSCO-Pad28)") (class "Default")
      (node (ref "U2") (pin "28") (pinfunction "OSCO_28") (pintype "output"))
    )
    (net (code "111") (name "unconnected-(U2-RI#-Pad6)") (class "Default")
      (node (ref "U2") (pin "6") (pinfunction "RI#_6") (pintype "input"))
    )
    (net (code "112") (name "unconnected-(U2-RTS#-Pad3)") (class "Default")
      (node (ref "U2") (pin "3") (pinfunction "RTS#_3") (pintype "output"))
    )
    (net (code "113") (name "unconnected-(USB-Pad1)") (class "Default")
      (node (ref "USB") (pin "1") (pinfunction "1_1") (pintype "passive"))
    )
  )
)
